# H_bridge_circuit.net
KiCad netlist of a schematic drawn in Altium Designer
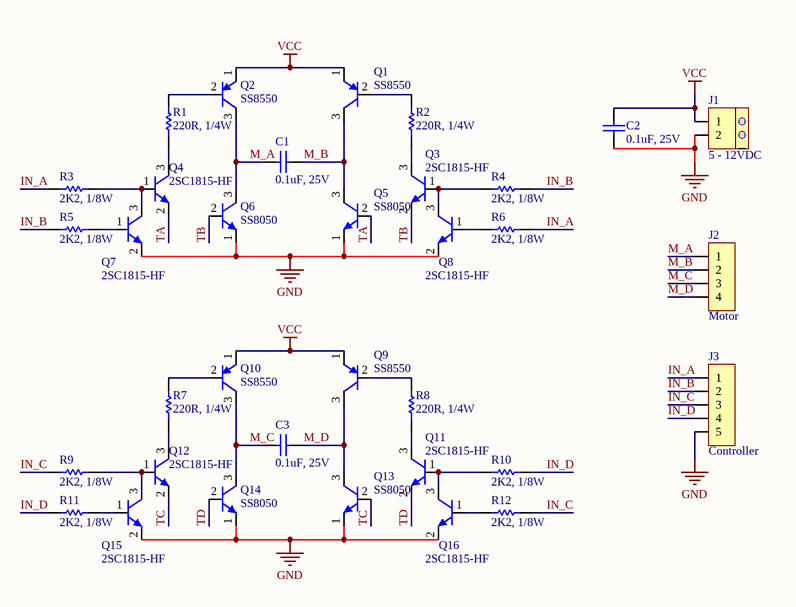
[diagram p0: H bridge circuit.SchDoc]

(export (version "E")
  (design (tool "Eeschema 10.0.6"))
  (components
    (comp (ref "C1")
      (value "0.1uF, 25V")
      (footprint "C0_1uF")
      (description "CAP Y5P CAPNTO 0.1uF 25V 20%")
      (fields (field (name "Comment") "5WF104MABAA"))
      (libsource (lib "Sau_Capacitors") (part "5WF104MABAA"))
    )
    (comp (ref "C2")
      (value "0.1uF, 25V")
      (footprint "C0_1uF")
      (description "CAP Y5P CAPNTO 0.1uF 25V 20%")
      (fields (field (name "Comment") "5WF104MABAA"))
      (libsource (lib "Sau_Capacitors") (part "5WF104MABAA"))
    )
    (comp (ref "C3")
      (value "0.1uF, 25V")
      (footprint "C0_1uF")
      (description "CAP Y5P CAPNTO 0.1uF 25V 20%")
      (fields (field (name "Comment") "5WF104MABAA"))
      (libsource (lib "Sau_Capacitors") (part "5WF104MABAA"))
    )
    (comp (ref "J1")
      (value "5 - 12VDC")
      (footprint "CON2")
      (description "Terminal Block 2 Poles 5.08mm Blue")
      (fields (field (name "Comment") "OSTTC-02-2162"))
      (libsource (lib "Sau_Connectors") (part "OSTTC-02-2162"))
    )
    (comp (ref "J2")
      (value "Motor")
      (footprint "Header_4")
      (description "Male Header 04 Pin 2.54mm Straight")
      (fields (field (name "Comment") "2012-254-1x04-SG"))
      (libsource (lib "Sau_Connectors") (part "2012-254-1x04-SG"))
    )
    (comp (ref "J3")
      (value "Controller")
      (footprint "Header_5")
      (description "Male Header 05 Pin 2.54mm Straight")
      (fields (field (name "Comment") "2012-254-1x05-SG"))
      (libsource (lib "Sau_Connectors") (part "2012-254-1x05-SG"))
    )
    (comp (ref "Q1")
      (value "SS8550")
      (footprint "SS8550")
      (description "Trans PNP -25V -1.5A TO-92")
      (libsource (lib "Sau_Transistors") (part "SS8550"))
    )
    (comp (ref "Q2")
      (value "SS8550")
      (footprint "SS8550")
      (description "Trans PNP -25V -1.5A TO-92")
      (libsource (lib "Sau_Transistors") (part "SS8550"))
    )
    (comp (ref "Q3")
      (value "2SC1815-HF")
      (footprint "2SC1815-HF")
      (description "Trans NPN 50V 150mA SOT-23")
      (libsource (lib "Sau_Transistors") (part "2SC1815-HF"))
    )
    (comp (ref "Q4")
      (value "2SC1815-HF")
      (footprint "2SC1815-HF")
      (description "Trans NPN 50V 150mA SOT-23")
      (libsource (lib "Sau_Transistors") (part "2SC1815-HF"))
    )
    (comp (ref "Q5")
      (value "SS8050")
      (footprint "SS8050")
      (description "Trans NPN 25V 1.5A TO-92")
      (libsource (lib "Sau_Transistors") (part "SS8050"))
    )
    (comp (ref "Q6")
      (value "SS8050")
      (footprint "SS8050")
      (description "Trans NPN 25V 1.5A TO-92")
      (libsource (lib "Sau_Transistors") (part "SS8050"))
    )
    (comp (ref "Q7")
      (value "2SC1815-HF")
      (footprint "2SC1815-HF")
      (description "Trans NPN 50V 150mA SOT-23")
      (libsource (lib "Sau_Transistors") (part "2SC1815-HF"))
    )
    (comp (ref "Q8")
      (value "2SC1815-HF")
      (footprint "2SC1815-HF")
      (description "Trans NPN 50V 150mA SOT-23")
      (libsource (lib "Sau_Transistors") (part "2SC1815-HF"))
    )
    (comp (ref "Q9")
      (value "SS8550")
      (footprint "SS8550")
      (description "Trans PNP -25V -1.5A TO-92")
      (libsource (lib "Sau_Transistors") (part "SS8550"))
    )
    (comp (ref "Q10")
      (value "SS8550")
      (footprint "SS8550")
      (description "Trans PNP -25V -1.5A TO-92")
      (libsource (lib "Sau_Transistors") (part "SS8550"))
    )
    (comp (ref "Q11")
      (value "2SC1815-HF")
      (footprint "2SC1815-HF")
      (description "Trans NPN 50V 150mA SOT-23")
      (libsource (lib "Sau_Transistors") (part "2SC1815-HF"))
    )
    (comp (ref "Q12")
      (value "2SC1815-HF")
      (footprint "2SC1815-HF")
      (description "Trans NPN 50V 150mA SOT-23")
      (libsource (lib "Sau_Transistors") (part "2SC1815-HF"))
    )
    (comp (ref "Q13")
      (value "SS8050")
      (footprint "SS8050")
      (description "Trans NPN 25V 1.5A TO-92")
      (libsource (lib "Sau_Transistors") (part "SS8050"))
    )
    (comp (ref "Q14")
      (value "SS8050")
      (footprint "SS8050")
      (description "Trans NPN 25V 1.5A TO-92")
      (libsource (lib "Sau_Transistors") (part "SS8050"))
    )
    (comp (ref "Q15")
      (value "2SC1815-HF")
      (footprint "2SC1815-HF")
      (description "Trans NPN 50V 150mA SOT-23")
      (libsource (lib "Sau_Transistors") (part "2SC1815-HF"))
    )
    (comp (ref "Q16")
      (value "2SC1815-HF")
      (footprint "2SC1815-HF")
      (description "Trans NPN 50V 150mA SOT-23")
      (libsource (lib "Sau_Transistors") (part "2SC1815-HF"))
    )
    (comp (ref "R1")
      (value "220R, 1/4W")
      (footprint "Res AXIAL-0.3")
      (description "RES CF AXIAL-0.3 5% 1/4W 220R")
      (fields (field (name "Comment") "CF1/4W220RJ25"))
      (libsource (lib "Sau_Resistors") (part "CF1/4W220RJ25"))
    )
    (comp (ref "R2")
      (value "220R, 1/4W")
      (footprint "Res AXIAL-0.3")
      (description "RES CF AXIAL-0.3 5% 1/4W 220R")
      (fields (field (name "Comment") "CF1/4W220RJ25"))
      (libsource (lib "Sau_Resistors") (part "CF1/4W220RJ25"))
    )
    (comp (ref "R3")
      (value "2K2, 1/8W")
      (footprint "RESC2012L")
      (description "RES CR 0805 5% 1/8W 2K2")
      (fields (field (name "Comment") "CR05JL7-2K2"))
      (libsource (lib "Sau_Resistors") (part "CR05JL7-2K2"))
    )
    (comp (ref "R4")
      (value "2K2, 1/8W")
      (footprint "RESC2012L")
      (description "RES CR 0805 5% 1/8W 2K2")
      (fields (field (name "Comment") "CR05JL7-2K2"))
      (libsource (lib "Sau_Resistors") (part "CR05JL7-2K2"))
    )
    (comp (ref "R5")
      (value "2K2, 1/8W")
      (footprint "RESC2012L")
      (description "RES CR 0805 5% 1/8W 2K2")
      (fields (field (name "Comment") "CR05JL7-2K2"))
      (libsource (lib "Sau_Resistors") (part "CR05JL7-2K2"))
    )
    (comp (ref "R6")
      (value "2K2, 1/8W")
      (footprint "RESC2012L")
      (description "RES CR 0805 5% 1/8W 2K2")
      (fields (field (name "Comment") "CR05JL7-2K2"))
      (libsource (lib "Sau_Resistors") (part "CR05JL7-2K2"))
    )
    (comp (ref "R7")
      (value "220R, 1/4W")
      (footprint "Res AXIAL-0.3")
      (description "RES CF AXIAL-0.3 5% 1/4W 220R")
      (fields (field (name "Comment") "CF1/4W220RJ25"))
      (libsource (lib "Sau_Resistors") (part "CF1/4W220RJ25"))
    )
    (comp (ref "R8")
      (value "220R, 1/4W")
      (footprint "Res AXIAL-0.3")
      (description "RES CF AXIAL-0.3 5% 1/4W 220R")
      (fields (field (name "Comment") "CF1/4W220RJ25"))
      (libsource (lib "Sau_Resistors") (part "CF1/4W220RJ25"))
    )
    (comp (ref "R9")
      (value "2K2, 1/8W")
      (footprint "RESC2012L")
      (description "RES CR 0805 5% 1/8W 2K2")
      (fields (field (name "Comment") "CR05JL7-2K2"))
      (libsource (lib "Sau_Resistors") (part "CR05JL7-2K2"))
    )
    (comp (ref "R10")
      (value "2K2, 1/8W")
      (footprint "RESC2012L")
      (description "RES CR 0805 5% 1/8W 2K2")
      (fields (field (name "Comment") "CR05JL7-2K2"))
      (libsource (lib "Sau_Resistors") (part "CR05JL7-2K2"))
    )
    (comp (ref "R11")
      (value "2K2, 1/8W")
      (footprint "RESC2012L")
      (description "RES CR 0805 5% 1/8W 2K2")
      (fields (field (name "Comment") "CR05JL7-2K2"))
      (libsource (lib "Sau_Resistors") (part "CR05JL7-2K2"))
    )
    (comp (ref "R12")
      (value "2K2, 1/8W")
      (footprint "RESC2012L")
      (description "RES CR 0805 5% 1/8W 2K2")
      (fields (field (name "Comment") "CR05JL7-2K2"))
      (libsource (lib "Sau_Resistors") (part "CR05JL7-2K2"))
    )
  )
  (nets
    (net (code "1") (name "/IN_A") (class "Default")
      (node (ref "J3") (pin "1") (pinfunction "1_1") (pintype "passive"))
      (node (ref "R3") (pin "1") (pinfunction "1_1") (pintype "passive"))
      (node (ref "R6") (pin "2") (pinfunction "2_2") (pintype "passive"))
    )
    (net (code "2") (name "/IN_B") (class "Default")
      (node (ref "J3") (pin "2") (pinfunction "2_2") (pintype "passive"))
      (node (ref "R4") (pin "2") (pinfunction "2_2") (pintype "passive"))
      (node (ref "R5") (pin "1") (pinfunction "1_1") (pintype "passive"))
    )
    (net (code "3") (name "/IN_C") (class "Default")
      (node (ref "J3") (pin "3") (pinfunction "3_3") (pintype "passive"))
      (node (ref "R12") (pin "2") (pinfunction "2_2") (pintype "passive"))
      (node (ref "R9") (pin "1") (pinfunction "1_1") (pintype "passive"))
    )
    (net (code "4") (name "/IN_D") (class "Default")
      (node (ref "J3") (pin "4") (pinfunction "4_4") (pintype "passive"))
      (node (ref "R10") (pin "2") (pinfunction "2_2") (pintype "passive"))
      (node (ref "R11") (pin "1") (pinfunction "1_1") (pintype "passive"))
    )
    (net (code "5") (name "/M_A") (class "Default")
      (node (ref "C1") (pin "1") (pinfunction "1_1") (pintype "passive"))
      (node (ref "J2") (pin "1") (pinfunction "1_1") (pintype "passive"))
      (node (ref "Q2") (pin "3") (pinfunction "C_3") (pintype "passive"))
      (node (ref "Q6") (pin "3") (pinfunction "C_3") (pintype "passive"))
    )
    (net (code "6") (name "/M_B") (class "Default")
      (node (ref "C1") (pin "2") (pinfunction "2_2") (pintype "passive"))
      (node (ref "J2") (pin "2") (pinfunction "2_2") (pintype "passive"))
      (node (ref "Q1") (pin "3") (pinfunction "C_3") (pintype "passive"))
      (node (ref "Q5") (pin "3") (pinfunction "C_3") (pintype "passive"))
    )
    (net (code "7") (name "/M_C") (class "Default")
      (node (ref "C3") (pin "1") (pinfunction "1_1") (pintype "passive"))
      (node (ref "J2") (pin "3") (pinfunction "3_3") (pintype "passive"))
      (node (ref "Q10") (pin "3") (pinfunction "C_3") (pintype "passive"))
      (node (ref "Q14") (pin "3") (pinfunction "C_3") (pintype "passive"))
    )
    (net (code "8") (name "/M_D") (class "Default")
      (node (ref "C3") (pin "2") (pinfunction "2_2") (pintype "passive"))
      (node (ref "J2") (pin "4") (pinfunction "4_4") (pintype "passive"))
      (node (ref "Q13") (pin "3") (pinfunction "C_3") (pintype "passive"))
      (node (ref "Q9") (pin "3") (pinfunction "C_3") (pintype "passive"))
    )
    (net (code "9") (name "/TA") (class "Default")
      (node (ref "Q4") (pin "2") (pinfunction "E_2") (pintype "passive"))
      (node (ref "Q5") (pin "2") (pinfunction "B_2") (pintype "passive"))
    )
    (net (code "10") (name "/TB") (class "Default")
      (node (ref "Q3") (pin "2") (pinfunction "E_2") (pintype "passive"))
      (node (ref "Q6") (pin "2") (pinfunction "B_2") (pintype "passive"))
    )
    (net (code "11") (name "/TC") (class "Default")
      (node (ref "Q12") (pin "2") (pinfunction "E_2") (pintype "passive"))
      (node (ref "Q13") (pin "2") (pinfunction "B_2") (pintype "passive"))
    )
    (net (code "12") (name "/TD") (class "Default")
      (node (ref "Q11") (pin "2") (pinfunction "E_2") (pintype "passive"))
      (node (ref "Q14") (pin "2") (pinfunction "B_2") (pintype "passive"))
    )
    (net (code "13") (name "GND") (class "Default")
      (node (ref "C2") (pin "1") (pinfunction "1_1") (pintype "passive"))
      (node (ref "J1") (pin "2") (pinfunction "2_2") (pintype "passive"))
      (node (ref "J3") (pin "5") (pinfunction "5_5") (pintype "passive"))
      (node (ref "Q13") (pin "1") (pinfunction "E_1") (pintype "passive"))
      (node (ref "Q14") (pin "1") (pinfunction "E_1") (pintype "passive"))
      (node (ref "Q15") (pin "2") (pinfunction "E_2") (pintype "passive"))
      (node (ref "Q16") (pin "2") (pinfunction "E_2") (pintype "passive"))
      (node (ref "Q5") (pin "1") (pinfunction "E_1") (pintype "passive"))
      (node (ref "Q6") (pin "1") (pinfunction "E_1") (pintype "passive"))
      (node (ref "Q7") (pin "2") (pinfunction "E_2") (pintype "passive"))
      (node (ref "Q8") (pin "2") (pinfunction "E_2") (pintype "passive"))
    )
    (net (code "14") (name "Net-(Q1-B)") (class "Default")
      (node (ref "Q1") (pin "2") (pinfunction "B_2") (pintype "passive"))
      (node (ref "R2") (pin "2") (pinfunction "2_2") (pintype "passive"))
    )
    (net (code "15") (name "Net-(Q2-B)") (class "Default")
      (node (ref "Q2") (pin "2") (pinfunction "B_2") (pintype "passive"))
      (node (ref "R1") (pin "2") (pinfunction "2_2") (pintype "passive"))
    )
    (net (code "16") (name "Net-(Q3-B)") (class "Default")
      (node (ref "Q3") (pin "1") (pinfunction "B_1") (pintype "passive"))
      (node (ref "Q8") (pin "3") (pinfunction "C_3") (pintype "passive"))
      (node (ref "R4") (pin "1") (pinfunction "1_1") (pintype "passive"))
    )
    (net (code "17") (name "Net-(Q3-C)") (class "Default")
      (node (ref "Q3") (pin "3") (pinfunction "C_3") (pintype "passive"))
      (node (ref "R2") (pin "1") (pinfunction "1_1") (pintype "passive"))
    )
    (net (code "18") (name "Net-(Q4-B)") (class "Default")
      (node (ref "Q4") (pin "1") (pinfunction "B_1") (pintype "passive"))
      (node (ref "Q7") (pin "3") (pinfunction "C_3") (pintype "passive"))
      (node (ref "R3") (pin "2") (pinfunction "2_2") (pintype "passive"))
    )
    (net (code "19") (name "Net-(Q4-C)") (class "Default")
      (node (ref "Q4") (pin "3") (pinfunction "C_3") (pintype "passive"))
      (node (ref "R1") (pin "1") (pinfunction "1_1") (pintype "passive"))
    )
    (net (code "20") (name "Net-(Q7-B)") (class "Default")
      (node (ref "Q7") (pin "1") (pinfunction "B_1") (pintype "passive"))
      (node (ref "R5") (pin "2") (pinfunction "2_2") (pintype "passive"))
    )
    (net (code "21") (name "Net-(Q8-B)") (class "Default")
      (node (ref "Q8") (pin "1") (pinfunction "B_1") (pintype "passive"))
      (node (ref "R6") (pin "1") (pinfunction "1_1") (pintype "passive"))
    )
    (net (code "22") (name "Net-(Q9-B)") (class "Default")
      (node (ref "Q9") (pin "2") (pinfunction "B_2") (pintype "passive"))
      (node (ref "R8") (pin "2") (pinfunction "2_2") (pintype "passive"))
    )
    (net (code "23") (name "Net-(Q10-B)") (class "Default")
      (node (ref "Q10") (pin "2") (pinfunction "B_2") (pintype "passive"))
      (node (ref "R7") (pin "2") (pinfunction "2_2") (pintype "passive"))
    )
    (net (code "24") (name "Net-(Q11-B)") (class "Default")
      (node (ref "Q11") (pin "1") (pinfunction "B_1") (pintype "passive"))
      (node (ref "Q16") (pin "3") (pinfunction "C_3") (pintype "passive"))
      (node (ref "R10") (pin "1") (pinfunction "1_1") (pintype "passive"))
    )
    (net (code "25") (name "Net-(Q11-C)") (class "Default")
      (node (ref "Q11") (pin "3") (pinfunction "C_3") (pintype "passive"))
      (node (ref "R8") (pin "1") (pinfunction "1_1") (pintype "passive"))
    )
    (net (code "26") (name "Net-(Q12-B)") (class "Default")
      (node (ref "Q12") (pin "1") (pinfunction "B_1") (pintype "passive"))
      (node (ref "Q15") (pin "3") (pinfunction "C_3") (pintype "passive"))
      (node (ref "R9") (pin "2") (pinfunction "2_2") (pintype "passive"))
    )
    (net (code "27") (name "Net-(Q12-C)") (class "Default")
      (node (ref "Q12") (pin "3") (pinfunction "C_3") (pintype "passive"))
      (node (ref "R7") (pin "1") (pinfunction "1_1") (pintype "passive"))
    )
    (net (code "28") (name "Net-(Q15-B)") (class "Default")
      (node (ref "Q15") (pin "1") (pinfunction "B_1") (pintype "passive"))
      (node (ref "R11") (pin "2") (pinfunction "2_2") (pintype "passive"))
    )
    (net (code "29") (name "Net-(Q16-B)") (class "Default")
      (node (ref "Q16") (pin "1") (pinfunction "B_1") (pintype "passive"))
      (node (ref "R12") (pin "1") (pinfunction "1_1") (pintype "passive"))
    )
    (net (code "30") (name "VCC") (class "Default")
      (node (ref "C2") (pin "2") (pinfunction "2_2") (pintype "passive"))
      (node (ref "J1") (pin "1") (pinfunction "1_1") (pintype "passive"))
      (node (ref "Q1") (pin "1") (pinfunction "E_1") (pintype "passive"))
      (node (ref "Q10") (pin "1") (pinfunction "E_1") (pintype "passive"))
      (node (ref "Q2") (pin "1") (pinfunction "E_1") (pintype "passive"))
      (node (ref "Q9") (pin "1") (pinfunction "E_1") (pintype "passive"))
    )
  )
)
